# Wifi.net
KiCad netlist of a schematic drawn in Altium Designer
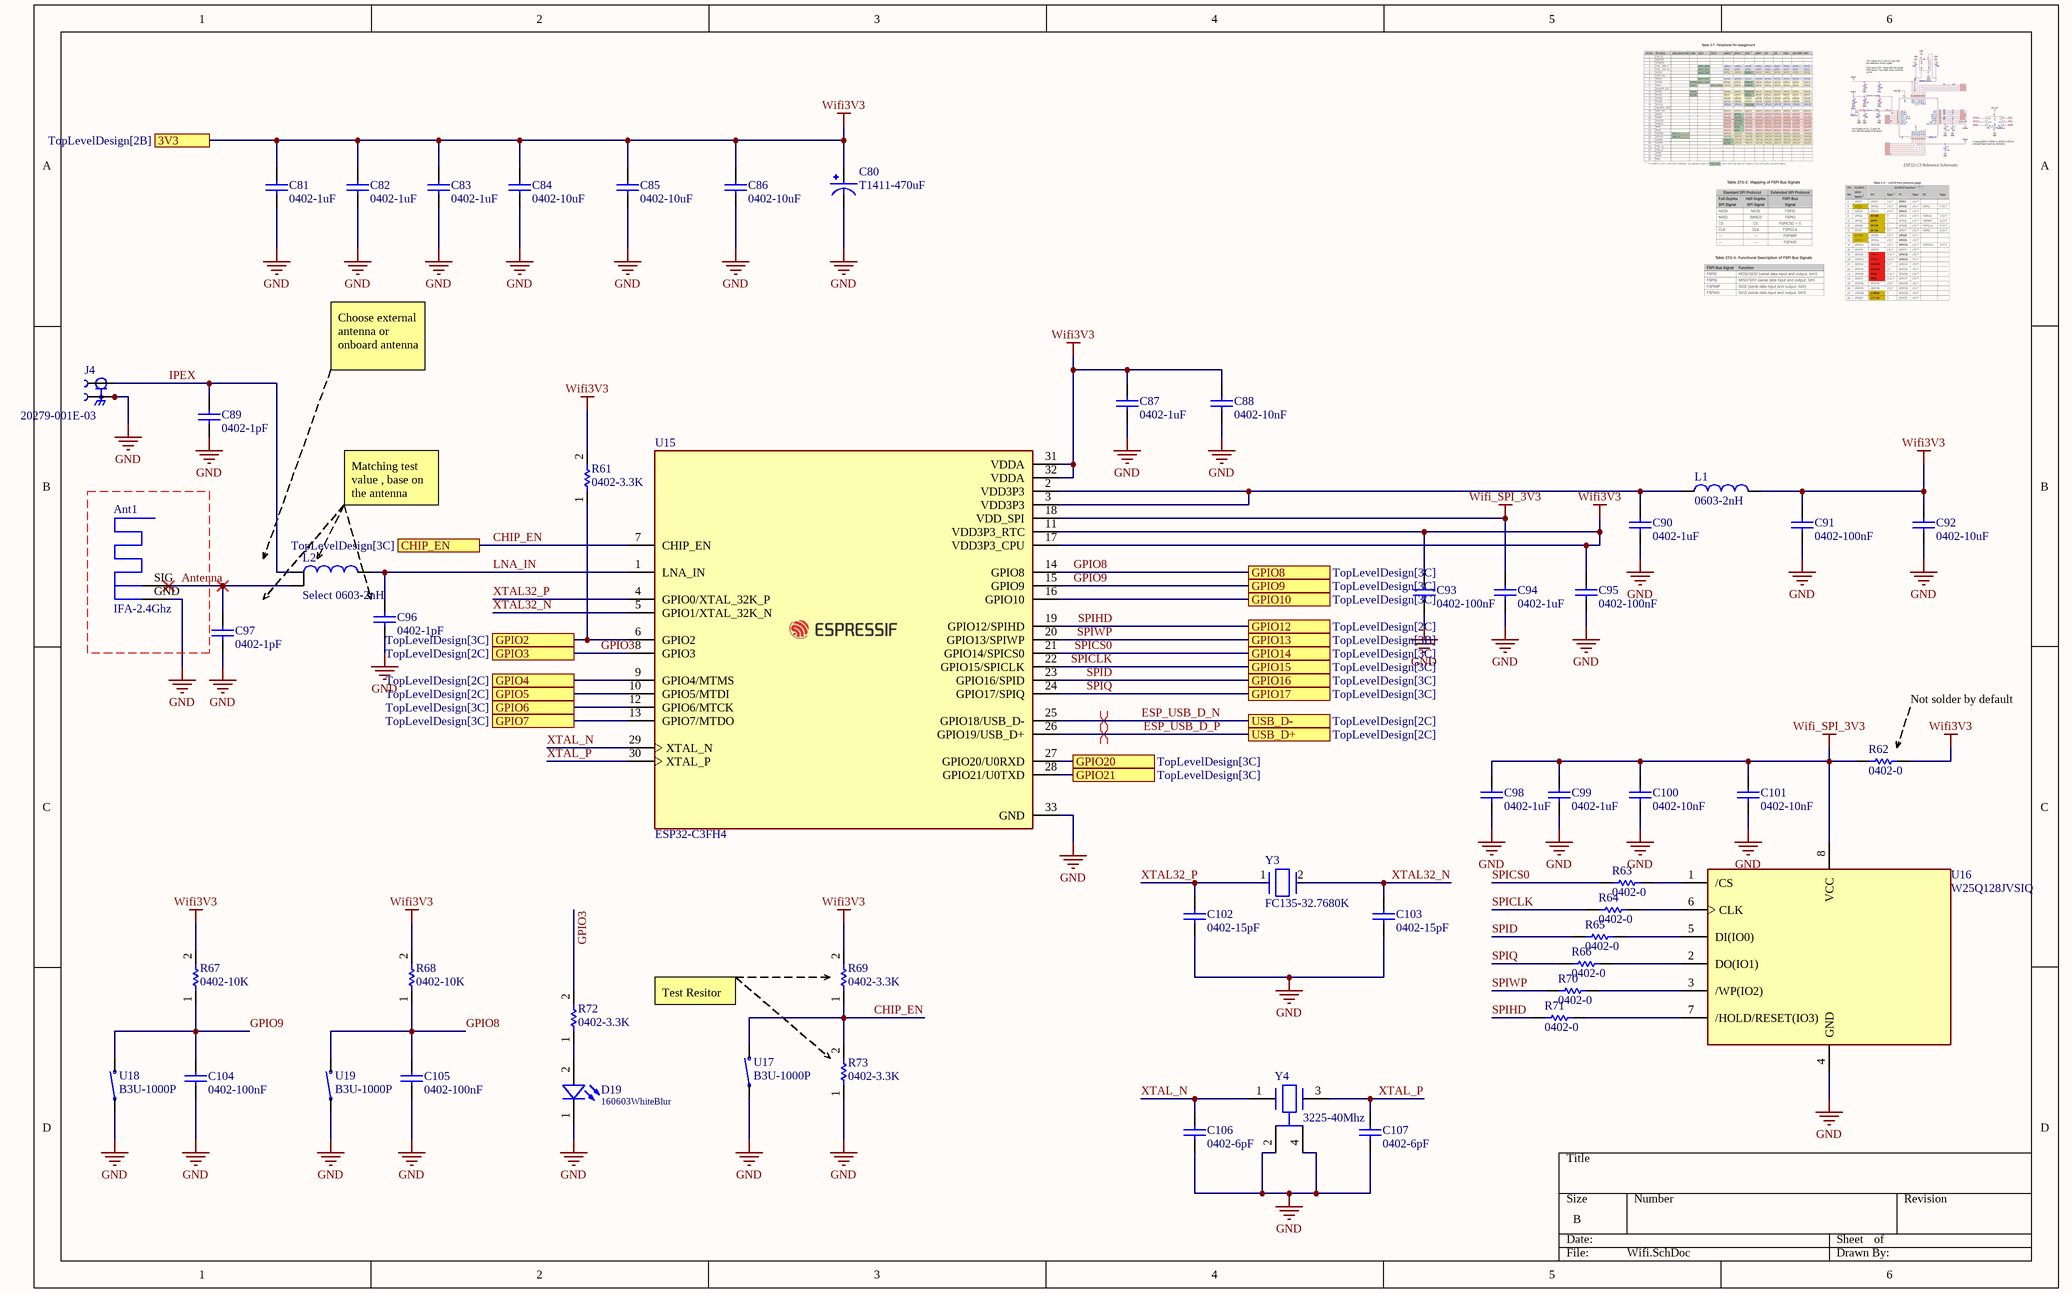
[diagram p0: Wifi.SchDoc]

(export (version "E")
  (design (tool "Eeschema 10.0.6"))
  (components
    (comp (ref "Ant1")
      (value "IFA-2.4Ghz")
      (footprint "IFA-2.4Ghz-Footprint-1")
      (description "Antenna Invert F 2.4Ghz")
      (libsource (lib "Tin Tran") (part "IFA-2.4Ghz"))
    )
    (comp (ref "C80")
      (value "T1411-470uF")
      (footprint "CAPPC3528X210N")
      (description "470 µF Molded Tantalum Polymer Capacitor 25 V 1411 (3528 Metric), 1210 150mOhm @ 100kHz")
      (fields (field (name "MP") "TCJB106M025R0150") (field (name "MF") "AVX"))
      (libsource (lib "Tin Tran") (part "T1411-10uF"))
    )
    (comp (ref "C81")
      (value "0402-1uF")
      (footprint "CAPC0402(1005)60_N")
      (description "Capacitor 1uF 0402s")
      (fields (field (name "TOLERANCE") "20%"))
      (libsource (lib "Tin Tran") (part "0402"))
    )
    (comp (ref "C82")
      (value "0402-1uF")
      (footprint "CAPC0402(1005)60_N")
      (description "Capacitor 1uF 0402s")
      (fields (field (name "TOLERANCE") "20%"))
      (libsource (lib "Tin Tran") (part "0402"))
    )
    (comp (ref "C83")
      (value "0402-1uF")
      (footprint "CAPC0402(1005)60_N")
      (description "Capacitor 1uF 0402s")
      (fields (field (name "TOLERANCE") "20%"))
      (libsource (lib "Tin Tran") (part "0402"))
    )
    (comp (ref "C84")
      (value "0402-10uF")
      (footprint "CAPC0402(1005)60_N")
      (description "Capacitor 10uF 0402s")
      (fields (field (name "TOLERANCE") "20%"))
      (libsource (lib "Tin Tran") (part "0402"))
    )
    (comp (ref "C85")
      (value "0402-10uF")
      (footprint "CAPC0402(1005)60_N")
      (description "Capacitor 10uF 0402s")
      (fields (field (name "TOLERANCE") "20%"))
      (libsource (lib "Tin Tran") (part "0402"))
    )
    (comp (ref "C86")
      (value "0402-10uF")
      (footprint "CAPC0402(1005)60_N")
      (description "Capacitor 10uF 0402s")
      (fields (field (name "TOLERANCE") "20%"))
      (libsource (lib "Tin Tran") (part "0402"))
    )
    (comp (ref "C87")
      (value "0402-1uF")
      (footprint "CAPC0402(1005)60_N")
      (description "Capacitor 1uF 0402s")
      (fields (field (name "TOLERANCE") "20%"))
      (libsource (lib "Tin Tran") (part "0402"))
    )
    (comp (ref "C88")
      (value "0402-10nF")
      (footprint "CAPC0402(1005)60_N")
      (description "Capacitor 10nF 0402")
      (fields (field (name "TOLERANCE") "20%"))
      (libsource (lib "Tin Tran") (part "0402"))
    )
    (comp (ref "C89")
      (value "0402-1pF")
      (footprint "CAPC0402(1005)60_N")
      (description "Capacitor 1pF 0402")
      (fields (field (name "TOLERANCE") "20%"))
      (libsource (lib "Tin Tran") (part "0402"))
    )
    (comp (ref "C90")
      (value "0402-1uF")
      (footprint "CAPC0402(1005)60_N")
      (description "Capacitor 1uF 0402s")
      (fields (field (name "TOLERANCE") "20%"))
      (libsource (lib "Tin Tran") (part "0402"))
    )
    (comp (ref "C91")
      (value "0402-100nF")
      (footprint "CAPC0402(1005)60_N")
      (description "Capacitor 100nF 0402")
      (fields (field (name "TOLERANCE") "20%"))
      (libsource (lib "Tin Tran") (part "0402"))
    )
    (comp (ref "C92")
      (value "0402-10uF")
      (footprint "CAPC0402(1005)60_N")
      (description "Capacitor 10uF 0402s")
      (fields (field (name "TOLERANCE") "20%"))
      (libsource (lib "Tin Tran") (part "0402"))
    )
    (comp (ref "C93")
      (value "0402-100nF")
      (footprint "CAPC0402(1005)60_N")
      (description "Capacitor 100nF 0402")
      (fields (field (name "TOLERANCE") "20%"))
      (libsource (lib "Tin Tran") (part "0402"))
    )
    (comp (ref "C94")
      (value "0402-1uF")
      (footprint "CAPC0402(1005)60_N")
      (description "Capacitor 1uF 0402s")
      (fields (field (name "TOLERANCE") "20%"))
      (libsource (lib "Tin Tran") (part "0402"))
    )
    (comp (ref "C95")
      (value "0402-100nF")
      (footprint "CAPC0402(1005)60_N")
      (description "Capacitor 100nF 0402")
      (fields (field (name "TOLERANCE") "20%"))
      (libsource (lib "Tin Tran") (part "0402"))
    )
    (comp (ref "C96")
      (value "0402-1pF")
      (footprint "CAPC0402(1005)60_N")
      (description "Capacitor 1pF 0402")
      (fields (field (name "TOLERANCE") "20%"))
      (libsource (lib "Tin Tran") (part "0402"))
    )
    (comp (ref "C97")
      (value "0402-1pF")
      (footprint "CAPC0402(1005)60_N")
      (description "Capacitor 1pF 0402")
      (fields (field (name "TOLERANCE") "20%"))
      (libsource (lib "Tin Tran") (part "0402"))
    )
    (comp (ref "C98")
      (value "0402-1uF")
      (footprint "CAPC0402(1005)60_N")
      (description "Capacitor 1uF 0402s")
      (fields (field (name "TOLERANCE") "20%"))
      (libsource (lib "Tin Tran") (part "0402"))
    )
    (comp (ref "C99")
      (value "0402-1uF")
      (footprint "CAPC0402(1005)60_N")
      (description "Capacitor 1uF 0402s")
      (fields (field (name "TOLERANCE") "20%"))
      (libsource (lib "Tin Tran") (part "0402"))
    )
    (comp (ref "C100")
      (value "0402-10nF")
      (footprint "CAPC0402(1005)60_N")
      (description "Capacitor 10nF 0402")
      (fields (field (name "TOLERANCE") "20%"))
      (libsource (lib "Tin Tran") (part "0402"))
    )
    (comp (ref "C101")
      (value "0402-10nF")
      (footprint "CAPC0402(1005)60_N")
      (description "Capacitor 10nF 0402")
      (fields (field (name "TOLERANCE") "20%"))
      (libsource (lib "Tin Tran") (part "0402"))
    )
    (comp (ref "C102")
      (value "0402-15pF")
      (footprint "CAPC0402(1005)60_N")
      (description "Capacitor 15pF 0402")
      (fields (field (name "TOLERANCE") "20%"))
      (libsource (lib "Tin Tran") (part "Copy of 0402"))
    )
    (comp (ref "C103")
      (value "0402-15pF")
      (footprint "CAPC0402(1005)60_N")
      (description "Capacitor 15pF 0402")
      (fields (field (name "TOLERANCE") "20%"))
      (libsource (lib "Tin Tran") (part "Copy of 0402"))
    )
    (comp (ref "C104")
      (value "0402-100nF")
      (footprint "CAPC0402(1005)60_N")
      (description "Capacitor 100nF 0402")
      (fields (field (name "TOLERANCE") "20%"))
      (libsource (lib "Tin Tran") (part "0402"))
    )
    (comp (ref "C105")
      (value "0402-100nF")
      (footprint "CAPC0402(1005)60_N")
      (description "Capacitor 100nF 0402")
      (fields (field (name "TOLERANCE") "20%"))
      (libsource (lib "Tin Tran") (part "0402"))
    )
    (comp (ref "C106")
      (value "0402-6pF")
      (footprint "CAPC0402(1005)60_N")
      (description "Capacitor 6pF 0402")
      (fields (field (name "TOLERANCE") "20%"))
      (libsource (lib "Tin Tran") (part "0402"))
    )
    (comp (ref "C107")
      (value "0402-6pF")
      (footprint "CAPC0402(1005)60_N")
      (description "Capacitor 6pF 0402")
      (fields (field (name "TOLERANCE") "20%"))
      (libsource (lib "Tin Tran") (part "0402"))
    )
    (comp (ref "D19")
      (value "160603WhiteBlur")
      (footprint "WL-SMCW_0603_H=0.7mm")
      (description "WL-SMCW SMT Mono-color Chip LED Blur, size 0603, White")
      (libsource (lib "Tin Tran") (part "160603WhiteClear"))
    )
    (comp (ref "J4")
      (value "20279-001E-03")
      (footprint "IPEX_20279-001E-03")
      (fields (field (name "MF") "I-PEX"))
      (libsource (lib "Tin Tran") (part "20279-001E-03"))
    )
    (comp (ref "L1")
      (value "0603-2nH")
      (footprint "INDC1608X80N")
      (fields (field (name "MP") "DFE18SBN1R0ME0L"))
      (libsource (lib "Tin Tran") (part "DFE18SBN1R0ME0L"))
    )
    (comp (ref "L2")
      (value "Select 0603-2nH")
      (footprint "Copy of INDC1608X80N")
      (description "0603-2nH Selected")
      (fields (field (name "MP") "DFE18SBN1R0ME0L"))
      (libsource (lib "") (part "DFE18SBN1R0ME0L_1"))
    )
    (comp (ref "R61")
      (value "0402-3.3K")
      (footprint "R-0402-10K")
      (description "RES 0402 3.3K")
      (libsource (lib "") (part "0402_2"))
    )
    (comp (ref "R62")
      (value "0402-0")
      (footprint "R-0402-1K")
      (description "0402Resistor 0 Ohm")
      (libsource (lib "") (part "0402_1"))
    )
    (comp (ref "R63")
      (value "0402-0")
      (footprint "R-0402-1K")
      (description "0402Resistor 0 Ohm")
      (libsource (lib "") (part "0402_1"))
    )
    (comp (ref "R64")
      (value "0402-0")
      (footprint "R-0402-1K")
      (description "0402Resistor 0 Ohm")
      (libsource (lib "") (part "0402_1"))
    )
    (comp (ref "R65")
      (value "0402-0")
      (footprint "R-0402-1K")
      (description "0402Resistor 0 Ohm")
      (libsource (lib "") (part "0402_1"))
    )
    (comp (ref "R66")
      (value "0402-0")
      (footprint "R-0402-1K")
      (description "0402Resistor 0 Ohm")
      (libsource (lib "") (part "0402_1"))
    )
    (comp (ref "R67")
      (value "0402-10K")
      (footprint "R-0402-10K")
      (description "RES 0402 10K")
      (libsource (lib "") (part "0402_2"))
    )
    (comp (ref "R68")
      (value "0402-10K")
      (footprint "R-0402-10K")
      (description "RES 0402 10K")
      (libsource (lib "") (part "0402_2"))
    )
    (comp (ref "R69")
      (value "0402-3.3K")
      (footprint "R-0402-10K")
      (description "RES 0402 3.3K")
      (libsource (lib "") (part "0402_2"))
    )
    (comp (ref "R70")
      (value "0402-0")
      (footprint "R-0402-1K")
      (description "0402Resistor 0 Ohm")
      (libsource (lib "") (part "0402_1"))
    )
    (comp (ref "R71")
      (value "0402-0")
      (footprint "R-0402-1K")
      (description "0402Resistor 0 Ohm")
      (libsource (lib "") (part "0402_1"))
    )
    (comp (ref "R72")
      (value "0402-3.3K")
      (footprint "R-0402-10K")
      (description "RES 0402 3.3K")
      (libsource (lib "") (part "0402_2"))
    )
    (comp (ref "R73")
      (value "0402-3.3K")
      (footprint "R-0402-10K")
      (description "RES 0402 3.3K")
      (libsource (lib "") (part "0402_2"))
    )
    (comp (ref "U15")
      (value "ESP32-C3FH4")
      (footprint "QFN50P500X500X90-33N")
      (libsource (lib "Tin Tran") (part "ESP32-C3FH4"))
    )
    (comp (ref "U16")
      (value "W25Q128JVSIQ")
      (footprint "SOIC127P790X216-8N")
      (description "FLASH - NOR Memory IC 128Mb (16M x 8) SPI - Quad I/O, QPI, DTR 133 MHz 8-SOIC")
      (fields (field (name "MF") "Winbond Electronics"))
      (libsource (lib "Tin Tran") (part "W25Q128JVSIQ"))
    )
    (comp (ref "U17")
      (value "B3U-1000P")
      (footprint "SODFL4025X160N")
      (description "Switch Tactile N.O. SPST Round Button Gull Wing 0.05A 12VDC 1.5N SMD T/R")
      (fields (field (name "MP") "B3U1000P") (field (name "MF") "Omron"))
      (libsource (lib "Tin Tran") (part "B3U-1000P"))
    )
    (comp (ref "U18")
      (value "B3U-1000P")
      (footprint "SODFL4025X160N")
      (description "Switch Tactile N.O. SPST Round Button Gull Wing 0.05A 12VDC 1.5N SMD T/R")
      (fields (field (name "MP") "B3U1000P") (field (name "MF") "Omron"))
      (libsource (lib "Tin Tran") (part "B3U-1000P"))
    )
    (comp (ref "U19")
      (value "B3U-1000P")
      (footprint "SODFL4025X160N")
      (description "Switch Tactile N.O. SPST Round Button Gull Wing 0.05A 12VDC 1.5N SMD T/R")
      (fields (field (name "MP") "B3U1000P") (field (name "MF") "Omron"))
      (libsource (lib "Tin Tran") (part "B3U-1000P"))
    )
    (comp (ref "Y3")
      (value "FC135-32.7680K")
      (footprint "FP-FC-135-MFG")
      (description "Parallel - Fundamental Quartz Crystal, 0.032768MHz Nom")
      (libsource (lib "Tin Tran") (part "c23a69dc6c9e2f18f2079038eb95dd1"))
    )
    (comp (ref "Y4")
      (value "3225-40Mhz")
      (footprint "FP-NX3225SA-MFG")
      (description "CRYSTAL 40MHZ 8PF SMD")
      (fields (field (name "TOLERANCE") "15ppm") (field (name "MANUFACTURER") "NDK"))
      (libsource (lib "Tin Tran") (part "CMP-200220-000002-1"))
    )
  )
  (nets
    (net (code "1") (name "/Antenna") (class "Default")
      (node (ref "Ant1") (pin "SIG") (pinfunction "SIG_SIG") (pintype "passive"))
      (node (ref "C97") (pin "2") (pinfunction "2_2") (pintype "passive"))
      (node (ref "L2") (pin "3") (pinfunction "3_3") (pintype "passive"))
    )
    (net (code "2") (name "/CHIP_EN") (class "Default")
      (node (ref "R69") (pin "1") (pinfunction "1_1") (pintype "passive"))
      (node (ref "R73") (pin "2") (pinfunction "2_2") (pintype "passive"))
      (node (ref "U15") (pin "7") (pinfunction "CHIP_EN_7") (pintype "passive"))
      (node (ref "U17") (pin "2") (pinfunction "2_2") (pintype "passive"))
    )
    (net (code "3") (name "/ESP_USB_D_N") (class "Default")
      (node (ref "U15") (pin "25") (pinfunction "GPIO18/USB_D-_25") (pintype "passive"))
    )
    (net (code "4") (name "/ESP_USB_D_P") (class "Default")
      (node (ref "U15") (pin "26") (pinfunction "GPIO19/USB_D+_26") (pintype "passive"))
    )
    (net (code "5") (name "/GPIO2") (class "Default")
      (node (ref "R61") (pin "1") (pinfunction "1_1") (pintype "passive"))
      (node (ref "U15") (pin "6") (pinfunction "GPIO2_6") (pintype "passive"))
    )
    (net (code "6") (name "/GPIO3") (class "Default")
      (node (ref "R72") (pin "2") (pinfunction "2_2") (pintype "passive"))
      (node (ref "U15") (pin "8") (pinfunction "GPIO3_8") (pintype "passive"))
    )
    (net (code "7") (name "/GPIO4") (class "Default")
      (node (ref "U15") (pin "9") (pinfunction "GPIO4/MTMS_9") (pintype "passive"))
    )
    (net (code "8") (name "/GPIO5") (class "Default")
      (node (ref "U15") (pin "10") (pinfunction "GPIO5/MTDI_10") (pintype "passive"))
    )
    (net (code "9") (name "/GPIO6") (class "Default")
      (node (ref "U15") (pin "12") (pinfunction "GPIO6/MTCK_12") (pintype "passive"))
    )
    (net (code "10") (name "/GPIO7") (class "Default")
      (node (ref "U15") (pin "13") (pinfunction "GPIO7/MTDO_13") (pintype "passive"))
    )
    (net (code "11") (name "/GPIO8") (class "Default")
      (node (ref "C105") (pin "2") (pinfunction "2_2") (pintype "passive"))
      (node (ref "R68") (pin "1") (pinfunction "1_1") (pintype "passive"))
      (node (ref "U15") (pin "14") (pinfunction "GPIO8_14") (pintype "passive"))
      (node (ref "U19") (pin "2") (pinfunction "2_2") (pintype "passive"))
    )
    (net (code "12") (name "/GPIO9") (class "Default")
      (node (ref "C104") (pin "2") (pinfunction "2_2") (pintype "passive"))
      (node (ref "R67") (pin "1") (pinfunction "1_1") (pintype "passive"))
      (node (ref "U15") (pin "15") (pinfunction "GPIO9_15") (pintype "passive"))
      (node (ref "U18") (pin "2") (pinfunction "2_2") (pintype "passive"))
    )
    (net (code "13") (name "/GPIO10") (class "Default")
      (node (ref "U15") (pin "16") (pinfunction "GPIO10_16") (pintype "passive"))
    )
    (net (code "14") (name "/GPIO20") (class "Default")
      (node (ref "U15") (pin "27") (pinfunction "GPIO20/U0RXD_27") (pintype "passive"))
    )
    (net (code "15") (name "/GPIO21") (class "Default")
      (node (ref "U15") (pin "28") (pinfunction "GPIO21/U0TXD_28") (pintype "passive"))
    )
    (net (code "16") (name "/IPEX") (class "Default")
      (node (ref "C89") (pin "2") (pinfunction "2_2") (pintype "passive"))
      (node (ref "J4") (pin "1") (pinfunction "SIGNAL_1") (pintype "passive"))
      (node (ref "L2") (pin "1") (pinfunction "1_1") (pintype "passive"))
    )
    (net (code "17") (name "/LNA_IN") (class "Default")
      (node (ref "C96") (pin "2") (pinfunction "2_2") (pintype "passive"))
      (node (ref "L2") (pin "2") (pinfunction "2_2") (pintype "passive"))
      (node (ref "U15") (pin "1") (pinfunction "LNA_IN_1") (pintype "passive"))
    )
    (net (code "18") (name "/SPICLK") (class "Default")
      (node (ref "R64") (pin "1") (pinfunction "1_1") (pintype "passive"))
      (node (ref "U15") (pin "22") (pinfunction "GPIO15/SPICLK_22") (pintype "passive"))
    )
    (net (code "19") (name "/SPICS0") (class "Default")
      (node (ref "R63") (pin "1") (pinfunction "1_1") (pintype "passive"))
      (node (ref "U15") (pin "21") (pinfunction "GPIO14/SPICS0_21") (pintype "passive"))
    )
    (net (code "20") (name "/SPID") (class "Default")
      (node (ref "R65") (pin "1") (pinfunction "1_1") (pintype "passive"))
      (node (ref "U15") (pin "23") (pinfunction "GPIO16/SPID_23") (pintype "passive"))
    )
    (net (code "21") (name "/SPIHD") (class "Default")
      (node (ref "R71") (pin "1") (pinfunction "1_1") (pintype "passive"))
      (node (ref "U15") (pin "19") (pinfunction "GPIO12/SPIHD_19") (pintype "passive"))
    )
    (net (code "22") (name "/SPIQ") (class "Default")
      (node (ref "R66") (pin "1") (pinfunction "1_1") (pintype "passive"))
      (node (ref "U15") (pin "24") (pinfunction "GPIO17/SPIQ_24") (pintype "passive"))
    )
    (net (code "23") (name "/SPIWP") (class "Default")
      (node (ref "R70") (pin "1") (pinfunction "1_1") (pintype "passive"))
      (node (ref "U15") (pin "20") (pinfunction "GPIO13/SPIWP_20") (pintype "passive"))
    )
    (net (code "24") (name "/XTAL32_N") (class "Default")
      (node (ref "C103") (pin "2") (pinfunction "2_2") (pintype "passive"))
      (node (ref "U15") (pin "5") (pinfunction "GPIO1/XTAL_32K_N_5") (pintype "passive"))
      (node (ref "Y3") (pin "2") (pinfunction "2_2") (pintype "passive"))
    )
    (net (code "25") (name "/XTAL32_P") (class "Default")
      (node (ref "C102") (pin "2") (pinfunction "2_2") (pintype "passive"))
      (node (ref "U15") (pin "4") (pinfunction "GPIO0/XTAL_32K_P_4") (pintype "passive"))
      (node (ref "Y3") (pin "1") (pinfunction "1_1") (pintype "passive"))
    )
    (net (code "26") (name "/XTAL_N") (class "Default")
      (node (ref "C106") (pin "2") (pinfunction "2_2") (pintype "passive"))
      (node (ref "U15") (pin "29") (pinfunction "XTAL_N_29") (pintype "passive"))
      (node (ref "Y4") (pin "1") (pinfunction "1_1") (pintype "passive"))
    )
    (net (code "27") (name "/XTAL_P") (class "Default")
      (node (ref "C107") (pin "2") (pinfunction "2_2") (pintype "passive"))
      (node (ref "U15") (pin "30") (pinfunction "XTAL_P_30") (pintype "passive"))
      (node (ref "Y4") (pin "3") (pinfunction "3_3") (pintype "passive"))
    )
    (net (code "28") (name "GND") (class "Default")
      (node (ref "Ant1") (pin "GND") (pinfunction "GND_GND") (pintype "passive"))
      (node (ref "C100") (pin "1") (pinfunction "1_1") (pintype "passive"))
      (node (ref "C101") (pin "1") (pinfunction "1_1") (pintype "passive"))
      (node (ref "C102") (pin "1") (pinfunction "1_1") (pintype "passive"))
      (node (ref "C103") (pin "1") (pinfunction "1_1") (pintype "passive"))
      (node (ref "C104") (pin "1") (pinfunction "1_1") (pintype "passive"))
      (node (ref "C105") (pin "1") (pinfunction "1_1") (pintype "passive"))
      (node (ref "C106") (pin "1") (pinfunction "1_1") (pintype "passive"))
      (node (ref "C107") (pin "1") (pinfunction "1_1") (pintype "passive"))
      (node (ref "C80") (pin "2") (pinfunction "2_2") (pintype "passive"))
      (node (ref "C81") (pin "1") (pinfunction "1_1") (pintype "passive"))
      (node (ref "C82") (pin "1") (pinfunction "1_1") (pintype "passive"))
      (node (ref "C83") (pin "1") (pinfunction "1_1") (pintype "passive"))
      (node (ref "C84") (pin "1") (pinfunction "1_1") (pintype "passive"))
      (node (ref "C85") (pin "1") (pinfunction "1_1") (pintype "passive"))
      (node (ref "C86") (pin "1") (pinfunction "1_1") (pintype "passive"))
      (node (ref "C87") (pin "1") (pinfunction "1_1") (pintype "passive"))
      (node (ref "C88") (pin "1") (pinfunction "1_1") (pintype "passive"))
      (node (ref "C89") (pin "1") (pinfunction "1_1") (pintype "passive"))
      (node (ref "C90") (pin "1") (pinfunction "1_1") (pintype "passive"))
      (node (ref "C91") (pin "1") (pinfunction "1_1") (pintype "passive"))
      (node (ref "C92") (pin "1") (pinfunction "1_1") (pintype "passive"))
      (node (ref "C93") (pin "1") (pinfunction "1_1") (pintype "passive"))
      (node (ref "C94") (pin "1") (pinfunction "1_1") (pintype "passive"))
      (node (ref "C95") (pin "1") (pinfunction "1_1") (pintype "passive"))
      (node (ref "C96") (pin "1") (pinfunction "1_1") (pintype "passive"))
      (node (ref "C97") (pin "1") (pinfunction "1_1") (pintype "passive"))
      (node (ref "C98") (pin "1") (pinfunction "1_1") (pintype "passive"))
      (node (ref "C99") (pin "1") (pinfunction "1_1") (pintype "passive"))
      (node (ref "D19") (pin "1") (pinfunction "K_1") (pintype "passive"))
      (node (ref "J4") (pin "2") (pinfunction "GROUND_2") (pintype "passive"))
      (node (ref "J4") (pin "3") (pinfunction "GROUND_3") (pintype "passive"))
      (node (ref "R73") (pin "1") (pinfunction "1_1") (pintype "passive"))
      (node (ref "U15") (pin "33") (pinfunction "GND_33") (pintype "passive"))
      (node (ref "U16") (pin "4") (pinfunction "GND_4") (pintype "power_in"))
      (node (ref "U17") (pin "1") (pinfunction "1_1") (pintype "passive"))
      (node (ref "U18") (pin "1") (pinfunction "1_1") (pintype "passive"))
      (node (ref "U19") (pin "1") (pinfunction "1_1") (pintype "passive"))
      (node (ref "Y4") (pin "2") (pinfunction "GND_2") (pintype "power_in"))
      (node (ref "Y4") (pin "4") (pinfunction "GND_4") (pintype "power_in"))
    )
    (net (code "29") (name "Net-(C90-Pad2)") (class "Default")
      (node (ref "C90") (pin "2") (pinfunction "2_2") (pintype "passive"))
      (node (ref "L1") (pin "1") (pinfunction "1_1") (pintype "passive"))
      (node (ref "U15") (pin "2") (pinfunction "VDD3P3_2") (pintype "passive"))
      (node (ref "U15") (pin "3") (pinfunction "VDD3P3_3") (pintype "passive"))
    )
    (net (code "30") (name "Net-(D19-A)") (class "Default")
      (node (ref "D19") (pin "2") (pinfunction "A_2") (pintype "passive"))
      (node (ref "R72") (pin "1") (pinfunction "1_1") (pintype "passive"))
    )
    (net (code "31") (name "Net-(U16-CLK)") (class "Default")
      (node (ref "R64") (pin "2") (pinfunction "2_2") (pintype "passive"))
      (node (ref "U16") (pin "6") (pinfunction "CLK_6") (pintype "passive"))
    )
    (net (code "32") (name "Net-(U16-DI(IO0))") (class "Default")
      (node (ref "R65") (pin "2") (pinfunction "2_2") (pintype "passive"))
      (node (ref "U16") (pin "5") (pinfunction "DI(IO0)_5") (pintype "passive"))
    )
    (net (code "33") (name "Net-(U16-DO(IO1))") (class "Default")
      (node (ref "R66") (pin "2") (pinfunction "2_2") (pintype "passive"))
      (node (ref "U16") (pin "2") (pinfunction "DO(IO1)_2") (pintype "passive"))
    )
    (net (code "34") (name "Net-(U16-{slash}CS)") (class "Default")
      (node (ref "R63") (pin "2") (pinfunction "2_2") (pintype "passive"))
      (node (ref "U16") (pin "1") (pinfunction "/CS_1") (pintype "passive"))
    )
    (net (code "35") (name "Net-(U16-{slash}HOLD{slash}RESET(IO3))") (class "Default")
      (node (ref "R71") (pin "2") (pinfunction "2_2") (pintype "passive"))
      (node (ref "U16") (pin "7") (pinfunction "/HOLD/RESET(IO3)_7") (pintype "passive"))
    )
    (net (code "36") (name "Net-(U16-{slash}WP(IO2))") (class "Default")
      (node (ref "R70") (pin "2") (pinfunction "2_2") (pintype "passive"))
      (node (ref "U16") (pin "3") (pinfunction "/WP(IO2)_3") (pintype "passive"))
    )
    (net (code "37") (name "Wifi3V3") (class "Default")
      (node (ref "C80") (pin "1") (pinfunction "1_1") (pintype "passive"))
      (node (ref "C81") (pin "2") (pinfunction "2_2") (pintype "passive"))
      (node (ref "C82") (pin "2") (pinfunction "2_2") (pintype "passive"))
      (node (ref "C83") (pin "2") (pinfunction "2_2") (pintype "passive"))
      (node (ref "C84") (pin "2") (pinfunction "2_2") (pintype "passive"))
      (node (ref "C85") (pin "2") (pinfunction "2_2") (pintype "passive"))
      (node (ref "C86") (pin "2") (pinfunction "2_2") (pintype "passive"))
      (node (ref "C87") (pin "2") (pinfunction "2_2") (pintype "passive"))
      (node (ref "C88") (pin "2") (pinfunction "2_2") (pintype "passive"))
      (node (ref "C91") (pin "2") (pinfunction "2_2") (pintype "passive"))
      (node (ref "C92") (pin "2") (pinfunction "2_2") (pintype "passive"))
      (node (ref "C93") (pin "2") (pinfunction "2_2") (pintype "passive"))
      (node (ref "C95") (pin "2") (pinfunction "2_2") (pintype "passive"))
      (node (ref "L1") (pin "2") (pinfunction "2_2") (pintype "passive"))
      (node (ref "R61") (pin "2") (pinfunction "2_2") (pintype "passive"))
      (node (ref "R62") (pin "2") (pinfunction "2_2") (pintype "passive"))
      (node (ref "R67") (pin "2") (pinfunction "2_2") (pintype "passive"))
      (node (ref "R68") (pin "2") (pinfunction "2_2") (pintype "passive"))
      (node (ref "R69") (pin "2") (pinfunction "2_2") (pintype "passive"))
      (node (ref "U15") (pin "11") (pinfunction "VDD3P3_RTC_11") (pintype "passive"))
      (node (ref "U15") (pin "17") (pinfunction "VDD3P3_CPU_17") (pintype "passive"))
      (node (ref "U15") (pin "31") (pinfunction "VDDA_31") (pintype "passive"))
      (node (ref "U15") (pin "32") (pinfunction "VDDA_32") (pintype "passive"))
    )
    (net (code "38") (name "Wifi_SPI_3V3") (class "Default")
      (node (ref "C100") (pin "2") (pinfunction "2_2") (pintype "passive"))
      (node (ref "C101") (pin "2") (pinfunction "2_2") (pintype "passive"))
      (node (ref "C94") (pin "2") (pinfunction "2_2") (pintype "passive"))
      (node (ref "C98") (pin "2") (pinfunction "2_2") (pintype "passive"))
      (node (ref "C99") (pin "2") (pinfunction "2_2") (pintype "passive"))
      (node (ref "R62") (pin "1") (pinfunction "1_1") (pintype "passive"))
      (node (ref "U15") (pin "18") (pinfunction "VDD_SPI_18") (pintype "passive"))
      (node (ref "U16") (pin "8") (pinfunction "VCC_8") (pintype "power_in"))
    )
  )
)
